# main.net
KiCad netlist of a schematic drawn in EAGLE
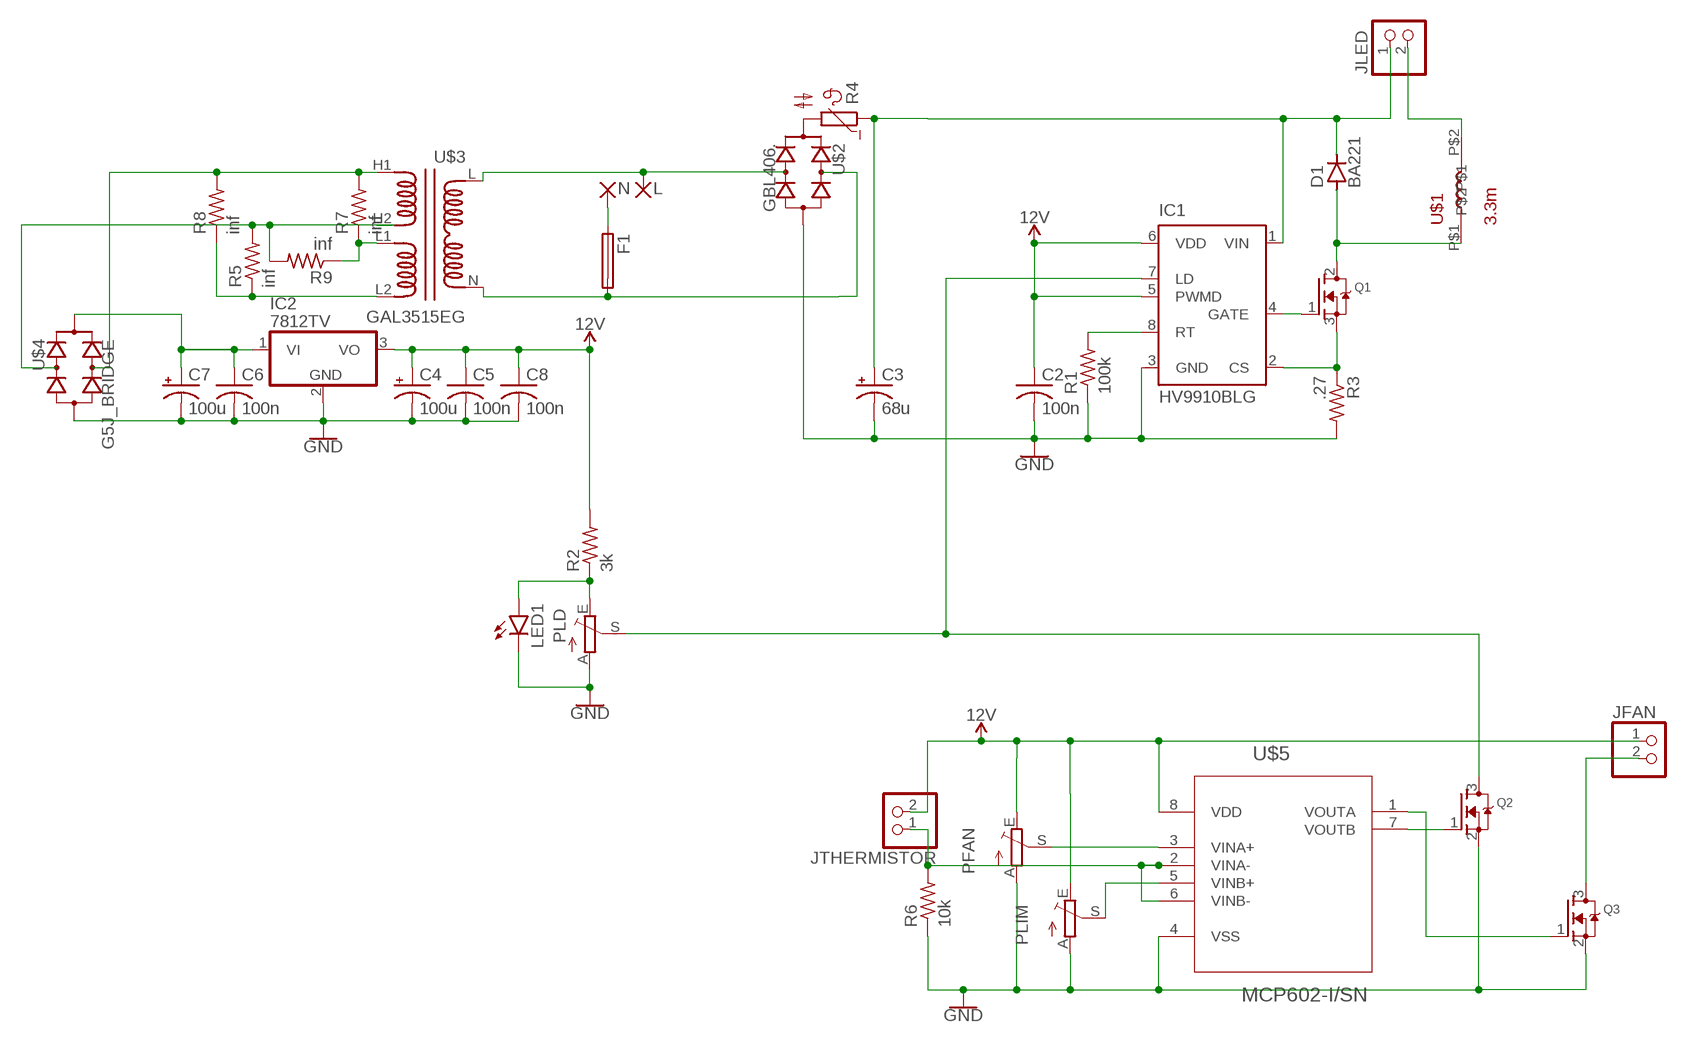
[diagram p0: schematic, sheet 1]

(export (version "E")
  (design (tool "Eeschema 10.0.6"))
  (components
    (comp (ref "C2")
      (value "100n")
      (footprint "eagle-import:C0603")
      (libsource (lib "eagle-import") (part "C-USC0603"))
    )
    (comp (ref "C3")
      (value "68u")
      (footprint "eagle-import:E7,5-16")
      (libsource (lib "eagle-import") (part "CPOL-USE7.5-16"))
    )
    (comp (ref "C4")
      (value "100u")
      (footprint "eagle-import:E3,5-8")
      (libsource (lib "eagle-import") (part "CPOL-USE3.5-8"))
    )
    (comp (ref "C5")
      (value "100n")
      (footprint "eagle-import:C0603")
      (libsource (lib "eagle-import") (part "C-USC0603"))
    )
    (comp (ref "C6")
      (value "100n")
      (footprint "eagle-import:C0603")
      (libsource (lib "eagle-import") (part "C-USC0603"))
    )
    (comp (ref "C7")
      (value "100u")
      (footprint "eagle-import:E3,5-8")
      (libsource (lib "eagle-import") (part "CPOL-USE3.5-8"))
    )
    (comp (ref "C8")
      (value "100n")
      (footprint "eagle-import:C0603")
      (libsource (lib "eagle-import") (part "C-USC0603"))
    )
    (comp (ref "D1")
      (value "BA221")
      (footprint "eagle-import:DO35-10")
      (libsource (lib "eagle-import") (part "BA221"))
    )
    (comp (ref "F1")
      (value "SH22,5A")
      (footprint "eagle-import:SH22,5A")
      (fields (field (name "MPN") "0031.7701.11"))
      (libsource (lib "eagle-import") (part "SH22,5A"))
    )
    (comp (ref "IC1")
      (value "HV9910BLG")
      (footprint "eagle-import:SOIC-08LG")
      (fields (field (name "MPN") "MXHV9910B"))
      (libsource (lib "eagle-import") (part "HV9910BLG"))
    )
    (comp (ref "IC2")
      (value "7812TV")
      (footprint "eagle-import:TO220V")
      (libsource (lib "eagle-import") (part "78TV12"))
    )
    (comp (ref "JFAN")
      (value "PINHD-1X2")
      (footprint "eagle-import:1X02")
      (libsource (lib "eagle-import") (part "PINHD-1X2"))
    )
    (comp (ref "JLED")
      (value "PINHD-1X2")
      (footprint "eagle-import:1X02")
      (libsource (lib "eagle-import") (part "PINHD-1X2"))
    )
    (comp (ref "JTHERMISTOR")
      (value "PINHD-1X2")
      (footprint "eagle-import:1X02")
      (libsource (lib "eagle-import") (part "PINHD-1X2"))
    )
    (comp (ref "L")
      (value "2,54/1,0")
      (footprint "eagle-import:2,54_1,0")
      (libsource (lib "eagle-import") (part "2,54/1,0"))
    )
    (comp (ref "LED1")
      (value "LED3MM")
      (footprint "eagle-import:LED3MM")
      (libsource (lib "eagle-import") (part "LED3MM"))
    )
    (comp (ref "N")
      (value "2,54/1,0")
      (footprint "eagle-import:2,54_1,0")
      (libsource (lib "eagle-import") (part "2,54/1,0"))
    )
    (comp (ref "PFAN")
      (value "TRIM_EU-B64Y")
      (footprint "eagle-import:B64Y")
      (libsource (lib "eagle-import") (part "TRIM_EU-B64Y"))
    )
    (comp (ref "PLD")
      (value "TRIM_EU-B64Y")
      (footprint "eagle-import:B64Y")
      (libsource (lib "eagle-import") (part "TRIM_EU-B64Y"))
    )
    (comp (ref "PLIM")
      (value "TRIM_EU-B64Y")
      (footprint "eagle-import:B64Y")
      (libsource (lib "eagle-import") (part "TRIM_EU-B64Y"))
    )
    (comp (ref "Q1")
      (value "MOSFET-NGDS_TO220V")
      (footprint "eagle-import:TO220V")
      (libsource (lib "eagle-import") (part "MOSFET-NGDS_TO220V"))
    )
    (comp (ref "Q2")
      (value "MOSFET-NREFLOW")
      (footprint "eagle-import:SOT23")
      (libsource (lib "eagle-import") (part "MOSFET-NREFLOW"))
    )
    (comp (ref "Q3")
      (value "MOSFET-NREFLOW")
      (footprint "eagle-import:SOT23")
      (libsource (lib "eagle-import") (part "MOSFET-NREFLOW"))
    )
    (comp (ref "R1")
      (value "100k")
      (footprint "eagle-import:R0603")
      (libsource (lib "eagle-import") (part "R-US_R0603"))
    )
    (comp (ref "R2")
      (value "3k")
      (footprint "eagle-import:0204_5")
      (libsource (lib "eagle-import") (part "R-US_0204/5"))
    )
    (comp (ref "R3")
      (value ".27")
      (footprint "eagle-import:0207_7")
      (libsource (lib "eagle-import") (part "R-US_0207/7"))
    )
    (comp (ref "R4")
      (value "B57164")
      (footprint "eagle-import:B57164")
      (fields (field (name "MPN") "B57164K474K52"))
      (libsource (lib "eagle-import") (part "B57164"))
    )
    (comp (ref "R5")
      (value "inf")
      (footprint "eagle-import:R0805")
      (libsource (lib "eagle-import") (part "R-US_R0805"))
    )
    (comp (ref "R6")
      (value "10k")
      (footprint "eagle-import:R0603")
      (libsource (lib "eagle-import") (part "R-US_R0603"))
    )
    (comp (ref "R7")
      (value "inf")
      (footprint "eagle-import:R0805")
      (libsource (lib "eagle-import") (part "R-US_R0805"))
    )
    (comp (ref "R8")
      (value "inf")
      (footprint "eagle-import:R0805")
      (libsource (lib "eagle-import") (part "R-US_R0805"))
    )
    (comp (ref "R9")
      (value "inf")
      (footprint "eagle-import:R0805")
      (libsource (lib "eagle-import") (part "R-US_R0805"))
    )
    (comp (ref "U$1")
      (value "3.3m")
      (footprint "eagle-import:3.3MH")
      (libsource (lib "eagle-import") (part "3.3MH"))
    )
    (comp (ref "U$2")
      (value "GBL406.")
      (footprint "eagle-import:GBL406")
      (libsource (lib "eagle-import") (part "GBL406."))
    )
    (comp (ref "U$3")
      (value "GAL3515EG")
      (footprint "eagle-import:GAL3515E")
      (libsource (lib "eagle-import") (part "GAL3515EG"))
    )
    (comp (ref "U$4")
      (value "G5J_BRIDGE")
      (footprint "eagle-import:G5J_BRIDGE")
      (libsource (lib "eagle-import") (part "G5J_BRIDGE"))
    )
    (comp (ref "U$5")
      (value "MCP602-I/SN")
      (footprint "eagle-import:SOIC127P600X175-8N")
      (libsource (lib "eagle-import") (part "MCP602-I/SN"))
    )
  )
  (nets
    (net (code "1") (name "12V") (class "Default")
      (node (ref "C2") (pin "1") (pinfunction "1_1") (pintype "passive"))
      (node (ref "C4") (pin "+") (pinfunction "+_+") (pintype "passive"))
      (node (ref "C5") (pin "1") (pinfunction "1_1") (pintype "passive"))
      (node (ref "C8") (pin "1") (pinfunction "1_1") (pintype "passive"))
      (node (ref "IC1") (pin "5") (pinfunction "PWMD_5") (pintype "input"))
      (node (ref "IC1") (pin "6") (pinfunction "VDD_6") (pintype "power_in"))
      (node (ref "IC2") (pin "3") (pinfunction "VO_3") (pintype "passive"))
      (node (ref "JFAN") (pin "1") (pinfunction "1_1") (pintype "passive"))
      (node (ref "JTHERMISTOR") (pin "2") (pinfunction "2_2") (pintype "passive"))
      (node (ref "PFAN") (pin "E") (pinfunction "E_E") (pintype "passive"))
      (node (ref "PLIM") (pin "E") (pinfunction "E_E") (pintype "passive"))
      (node (ref "R2") (pin "2") (pinfunction "2_2") (pintype "passive"))
      (node (ref "U$5") (pin "8") (pinfunction "VDD_8") (pintype "power_in"))
    )
    (net (code "2") (name "GND") (class "Default")
      (node (ref "C2") (pin "2") (pinfunction "2_2") (pintype "passive"))
      (node (ref "C3") (pin "-") (pinfunction "-_-") (pintype "passive"))
      (node (ref "C4") (pin "-") (pinfunction "-_-") (pintype "passive"))
      (node (ref "C5") (pin "2") (pinfunction "2_2") (pintype "passive"))
      (node (ref "C6") (pin "2") (pinfunction "2_2") (pintype "passive"))
      (node (ref "C7") (pin "-") (pinfunction "-_-") (pintype "passive"))
      (node (ref "C8") (pin "2") (pinfunction "2_2") (pintype "passive"))
      (node (ref "IC1") (pin "3") (pinfunction "GND_3") (pintype "power_in"))
      (node (ref "IC2") (pin "2") (pinfunction "GND_2") (pintype "passive"))
      (node (ref "LED1") (pin "K") (pinfunction "C_K") (pintype "passive"))
      (node (ref "PFAN") (pin "A") (pinfunction "A_A") (pintype "passive"))
      (node (ref "PLD") (pin "A") (pinfunction "A_A") (pintype "passive"))
      (node (ref "PLIM") (pin "A") (pinfunction "A_A") (pintype "passive"))
      (node (ref "Q2") (pin "2") (pinfunction "S_2") (pintype "bidirectional"))
      (node (ref "Q3") (pin "2") (pinfunction "S_2") (pintype "bidirectional"))
      (node (ref "R1") (pin "1") (pinfunction "1_1") (pintype "passive"))
      (node (ref "R3") (pin "2") (pinfunction "2_2") (pintype "passive"))
      (node (ref "R6") (pin "1") (pinfunction "1_1") (pintype "passive"))
      (node (ref "U$2") (pin "-") (pinfunction "-_-") (pintype "passive"))
      (node (ref "U$4") (pin "-") (pinfunction "-_-") (pintype "passive"))
      (node (ref "U$5") (pin "4") (pinfunction "VSS_4") (pintype "power_in"))
    )
    (net (code "3") (name "Net-(F1-Pad2)") (class "Default")
      (node (ref "F1") (pin "2") (pinfunction "2_2") (pintype "passive"))
      (node (ref "U$2") (pin "AC@1") (pinfunction "AC_AC@1") (pintype "passive"))
      (node (ref "U$3") (pin "N") (pinfunction "N_N") (pintype "passive"))
    )
    (net (code "4") (name "Net-(IC1-CS)") (class "Default")
      (node (ref "IC1") (pin "2") (pinfunction "CS_2") (pintype "input"))
      (node (ref "Q1") (pin "3") (pinfunction "S_3") (pintype "bidirectional"))
      (node (ref "R3") (pin "1") (pinfunction "1_1") (pintype "passive"))
    )
    (net (code "5") (name "Net-(IC1-GATE)") (class "Default")
      (node (ref "IC1") (pin "4") (pinfunction "GATE_4") (pintype "output"))
      (node (ref "Q1") (pin "1") (pinfunction "G_1") (pintype "bidirectional"))
    )
    (net (code "6") (name "Net-(IC1-LD)") (class "Default")
      (node (ref "IC1") (pin "7") (pinfunction "LD_7") (pintype "input"))
      (node (ref "PLD") (pin "S") (pinfunction "S_S") (pintype "passive"))
      (node (ref "Q2") (pin "3") (pinfunction "D_3") (pintype "bidirectional"))
    )
    (net (code "7") (name "Net-(IC1-RT)") (class "Default")
      (node (ref "IC1") (pin "8") (pinfunction "RT_8") (pintype "passive"))
      (node (ref "R1") (pin "2") (pinfunction "2_2") (pintype "passive"))
    )
    (net (code "8") (name "Net-(IC1-VIN)") (class "Default")
      (node (ref "C3") (pin "+") (pinfunction "+_+") (pintype "passive"))
      (node (ref "D1") (pin "C") (pinfunction "C_C") (pintype "passive"))
      (node (ref "IC1") (pin "1") (pinfunction "VIN_1") (pintype "input"))
      (node (ref "JLED") (pin "1") (pinfunction "1_1") (pintype "passive"))
      (node (ref "R4") (pin "1") (pinfunction "1_1") (pintype "passive"))
    )
    (net (code "9") (name "Net-(IC2-VI)") (class "Default")
      (node (ref "C6") (pin "1") (pinfunction "1_1") (pintype "passive"))
      (node (ref "C7") (pin "+") (pinfunction "+_+") (pintype "passive"))
      (node (ref "IC2") (pin "1") (pinfunction "VI_1") (pintype "input"))
      (node (ref "U$4") (pin "+") (pinfunction "+_+") (pintype "passive"))
    )
    (net (code "10") (name "Net-(JLED-Pad2)") (class "Default")
      (node (ref "JLED") (pin "2") (pinfunction "2_2") (pintype "passive"))
      (node (ref "U$1") (pin "P$2") (pinfunction "P$2_P$2") (pintype "bidirectional"))
    )
    (net (code "11") (name "Net-(L-P)") (class "Default")
      (node (ref "L") (pin "1") (pinfunction "P_1") (pintype "passive"))
      (node (ref "U$2") (pin "AC@2") (pinfunction "AC_AC@2") (pintype "passive"))
      (node (ref "U$3") (pin "L") (pinfunction "L_L") (pintype "passive"))
    )
    (net (code "12") (name "Net-(LED1-PadA)") (class "Default")
      (node (ref "LED1") (pin "A") (pinfunction "A_A") (pintype "passive"))
      (node (ref "PLD") (pin "E") (pinfunction "E_E") (pintype "passive"))
      (node (ref "R2") (pin "1") (pinfunction "1_1") (pintype "passive"))
    )
    (net (code "13") (name "Net-(N-P)") (class "Default")
      (node (ref "F1") (pin "1") (pinfunction "1_1") (pintype "passive"))
      (node (ref "N") (pin "1") (pinfunction "P_1") (pintype "passive"))
    )
    (net (code "14") (name "Net-(Q1-D)") (class "Default")
      (node (ref "D1") (pin "A") (pinfunction "A_A") (pintype "passive"))
      (node (ref "Q1") (pin "2") (pinfunction "D_2") (pintype "bidirectional"))
      (node (ref "U$1") (pin "P$1") (pinfunction "P$1_P$1") (pintype "bidirectional"))
    )
    (net (code "15") (name "Net-(Q2-G)") (class "Default")
      (node (ref "Q2") (pin "1") (pinfunction "G_1") (pintype "bidirectional"))
      (node (ref "U$5") (pin "7") (pinfunction "VOUTB_7") (pintype "output"))
    )
    (net (code "16") (name "Net-(Q3-D)") (class "Default")
      (node (ref "JFAN") (pin "2") (pinfunction "2_2") (pintype "passive"))
      (node (ref "Q3") (pin "3") (pinfunction "D_3") (pintype "bidirectional"))
    )
    (net (code "17") (name "Net-(Q3-G)") (class "Default")
      (node (ref "Q3") (pin "1") (pinfunction "G_1") (pintype "bidirectional"))
      (node (ref "U$5") (pin "1") (pinfunction "VOUTA_1") (pintype "output"))
    )
    (net (code "18") (name "Net-(R4-Pad2)") (class "Default")
      (node (ref "R4") (pin "2") (pinfunction "2_2") (pintype "passive"))
      (node (ref "U$2") (pin "+") (pinfunction "+_+") (pintype "passive"))
    )
    (net (code "19") (name "Net-(R5-Pad1)") (class "Default")
      (node (ref "R5") (pin "1") (pinfunction "1_1") (pintype "passive"))
      (node (ref "R8") (pin "1") (pinfunction "1_1") (pintype "passive"))
      (node (ref "U$3") (pin "L2") (pinfunction "L2_L2") (pintype "passive"))
    )
    (net (code "20") (name "Net-(R5-Pad2)") (class "Default")
      (node (ref "R5") (pin "2") (pinfunction "2_2") (pintype "passive"))
      (node (ref "R9") (pin "2") (pinfunction "2_2") (pintype "passive"))
      (node (ref "U$3") (pin "H2") (pinfunction "H2_H2") (pintype "passive"))
      (node (ref "U$4") (pin "AC1") (pinfunction "AC_AC1") (pintype "passive"))
    )
    (net (code "21") (name "Net-(R7-Pad1)") (class "Default")
      (node (ref "R7") (pin "1") (pinfunction "1_1") (pintype "passive"))
      (node (ref "R9") (pin "1") (pinfunction "1_1") (pintype "passive"))
      (node (ref "U$3") (pin "L1") (pinfunction "L1_L1") (pintype "passive"))
    )
    (net (code "22") (name "Net-(R7-Pad2)") (class "Default")
      (node (ref "R7") (pin "2") (pinfunction "2_2") (pintype "passive"))
      (node (ref "R8") (pin "2") (pinfunction "2_2") (pintype "passive"))
      (node (ref "U$3") (pin "H1") (pinfunction "H1_H1") (pintype "passive"))
      (node (ref "U$4") (pin "AC2") (pinfunction "AC_AC2") (pintype "passive"))
    )
    (net (code "23") (name "Net-(U$5-VINA+)") (class "Default")
      (node (ref "PFAN") (pin "S") (pinfunction "S_S") (pintype "passive"))
      (node (ref "U$5") (pin "3") (pinfunction "VINA+_3") (pintype "input"))
    )
    (net (code "24") (name "Net-(U$5-VINA-)") (class "Default")
      (node (ref "JTHERMISTOR") (pin "1") (pinfunction "1_1") (pintype "passive"))
      (node (ref "R6") (pin "2") (pinfunction "2_2") (pintype "passive"))
      (node (ref "U$5") (pin "2") (pinfunction "VINA-_2") (pintype "input"))
      (node (ref "U$5") (pin "6") (pinfunction "VINB-_6") (pintype "input"))
    )
    (net (code "25") (name "Net-(U$5-VINB+)") (class "Default")
      (node (ref "PLIM") (pin "S") (pinfunction "S_S") (pintype "passive"))
      (node (ref "U$5") (pin "5") (pinfunction "VINB+_5") (pintype "input"))
    )
  )
)
